# Piano_DIY_Project_Yay.net
KiCad netlist of a schematic drawn in EAGLE
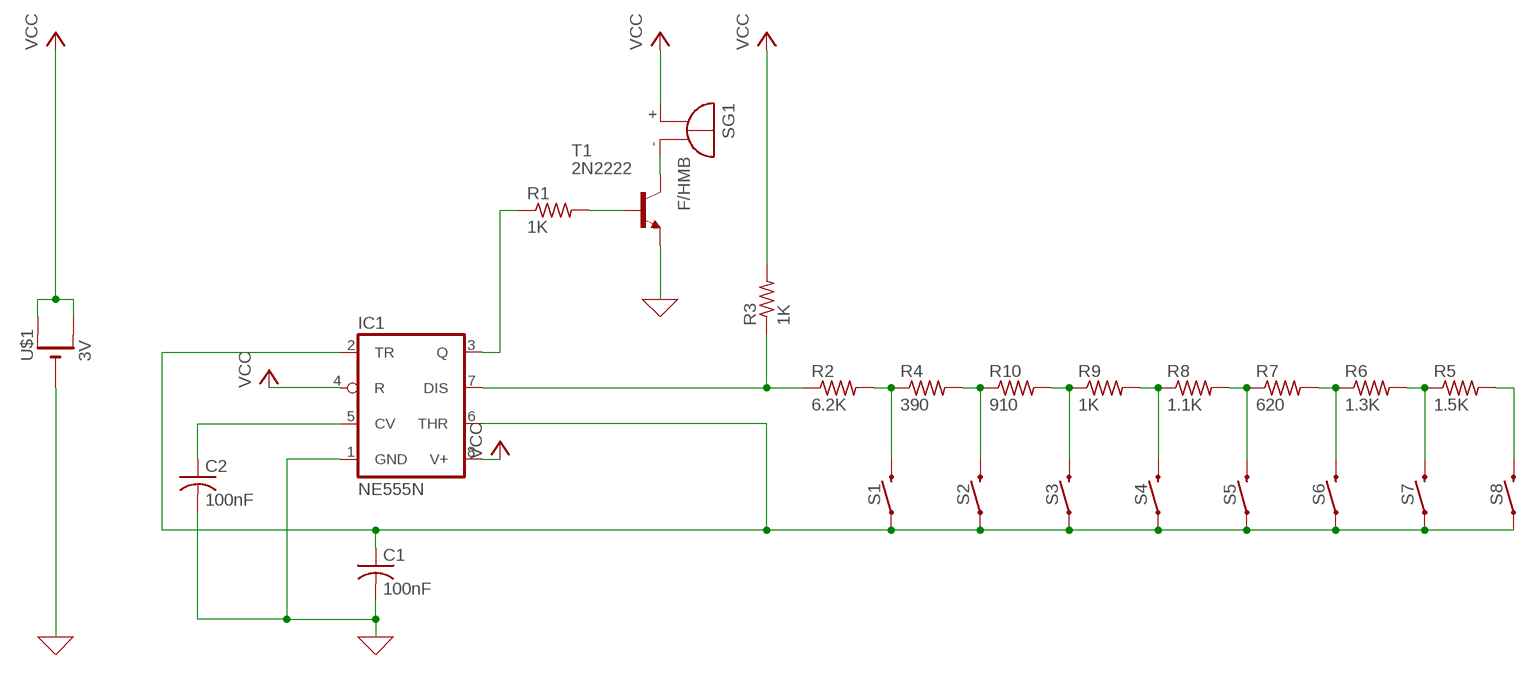
[diagram p0: schematic, sheet 1]

(export (version "E")
  (design (tool "Eeschema 10.0.6"))
  (components
    (comp (ref "C1")
      (value "100nF")
      (footprint "eagle-import:C025-025X050")
      (libsource (lib "eagle-import") (part "C-US025-025X050"))
    )
    (comp (ref "C2")
      (value "100nF")
      (footprint "eagle-import:C025-025X050")
      (libsource (lib "eagle-import") (part "C-US025-025X050"))
    )
    (comp (ref "IC1")
      (value "NE555N")
      (footprint "eagle-import:DIL08")
      (libsource (lib "eagle-import") (part "555NNE"))
    )
    (comp (ref "R1")
      (value "1K")
      (footprint "eagle-import:0207_10")
      (libsource (lib "eagle-import") (part "R-US_0207/10"))
    )
    (comp (ref "R2")
      (value "6.2K")
      (footprint "eagle-import:0207_10")
      (libsource (lib "eagle-import") (part "R-US_0207/10"))
    )
    (comp (ref "R3")
      (value "1K")
      (footprint "eagle-import:0207_10")
      (libsource (lib "eagle-import") (part "R-US_0207/10"))
    )
    (comp (ref "R4")
      (value "390")
      (footprint "eagle-import:0207_10")
      (libsource (lib "eagle-import") (part "R-US_0207/10"))
    )
    (comp (ref "R5")
      (value "1.5K")
      (footprint "eagle-import:0207_10")
      (libsource (lib "eagle-import") (part "R-US_0207/10"))
    )
    (comp (ref "R6")
      (value "1.3K")
      (footprint "eagle-import:0207_10")
      (libsource (lib "eagle-import") (part "R-US_0207/10"))
    )
    (comp (ref "R7")
      (value "620")
      (footprint "eagle-import:0207_10")
      (libsource (lib "eagle-import") (part "R-US_0207/10"))
    )
    (comp (ref "R8")
      (value "1.1K")
      (footprint "eagle-import:0207_10")
      (libsource (lib "eagle-import") (part "R-US_0207/10"))
    )
    (comp (ref "R9")
      (value "1K")
      (footprint "eagle-import:0207_10")
      (libsource (lib "eagle-import") (part "R-US_0207/10"))
    )
    (comp (ref "R10")
      (value "910")
      (footprint "eagle-import:0207_10")
      (libsource (lib "eagle-import") (part "R-US_0207/10"))
    )
    (comp (ref "S1")
      (value "MOMENTARY-SWITCH-SPST-PTH-6.0MM")
      (footprint "eagle-import:TACTILE_SWITCH_PTH_6.0MM")
      (libsource (lib "eagle-import") (part "MOMENTARY-SWITCH-SPST-PTH-6.0MM"))
    )
    (comp (ref "S2")
      (value "MOMENTARY-SWITCH-SPST-PTH-6.0MM")
      (footprint "eagle-import:TACTILE_SWITCH_PTH_6.0MM")
      (libsource (lib "eagle-import") (part "MOMENTARY-SWITCH-SPST-PTH-6.0MM"))
    )
    (comp (ref "S3")
      (value "MOMENTARY-SWITCH-SPST-PTH-6.0MM")
      (footprint "eagle-import:TACTILE_SWITCH_PTH_6.0MM")
      (libsource (lib "eagle-import") (part "MOMENTARY-SWITCH-SPST-PTH-6.0MM"))
    )
    (comp (ref "S4")
      (value "MOMENTARY-SWITCH-SPST-PTH-6.0MM")
      (footprint "eagle-import:TACTILE_SWITCH_PTH_6.0MM")
      (libsource (lib "eagle-import") (part "MOMENTARY-SWITCH-SPST-PTH-6.0MM"))
    )
    (comp (ref "S5")
      (value "MOMENTARY-SWITCH-SPST-PTH-6.0MM")
      (footprint "eagle-import:TACTILE_SWITCH_PTH_6.0MM")
      (libsource (lib "eagle-import") (part "MOMENTARY-SWITCH-SPST-PTH-6.0MM"))
    )
    (comp (ref "S6")
      (value "MOMENTARY-SWITCH-SPST-PTH-6.0MM")
      (footprint "eagle-import:TACTILE_SWITCH_PTH_6.0MM")
      (libsource (lib "eagle-import") (part "MOMENTARY-SWITCH-SPST-PTH-6.0MM"))
    )
    (comp (ref "S7")
      (value "MOMENTARY-SWITCH-SPST-PTH-6.0MM")
      (footprint "eagle-import:TACTILE_SWITCH_PTH_6.0MM")
      (libsource (lib "eagle-import") (part "MOMENTARY-SWITCH-SPST-PTH-6.0MM"))
    )
    (comp (ref "S8")
      (value "MOMENTARY-SWITCH-SPST-PTH-6.0MM")
      (footprint "eagle-import:TACTILE_SWITCH_PTH_6.0MM")
      (libsource (lib "eagle-import") (part "MOMENTARY-SWITCH-SPST-PTH-6.0MM"))
    )
    (comp (ref "SG1")
      (value "F/HMB")
      (footprint "eagle-import:F_HMB")
      (libsource (lib "eagle-import") (part "F/HMB"))
    )
    (comp (ref "T1")
      (value "2N2222")
      (footprint "eagle-import:TO92")
      (libsource (lib "eagle-import") (part "-NPN-TO92"))
    )
    (comp (ref "U$1")
      (value "3V")
      (footprint "eagle-import:CR1220-THM")
      (libsource (lib "eagle-import") (part "CR1220THM"))
    )
  )
  (nets
    (net (code "1") (name "GND") (class "Default")
      (node (ref "C1") (pin "2") (pinfunction "2_2") (pintype "passive"))
      (node (ref "C2") (pin "2") (pinfunction "2_2") (pintype "passive"))
      (node (ref "IC1") (pin "1") (pinfunction "GND_1") (pintype "power_in"))
      (node (ref "T1") (pin "1") (pinfunction "E_1") (pintype "passive"))
      (node (ref "U$1") (pin "-") (pinfunction "-_-") (pintype "passive"))
    )
    (net (code "2") (name "Net-(IC1-CV)") (class "Default")
      (node (ref "C2") (pin "1") (pinfunction "1_1") (pintype "passive"))
      (node (ref "IC1") (pin "5") (pinfunction "CV_5") (pintype "input"))
    )
    (net (code "3") (name "Net-(IC1-DIS)") (class "Default")
      (node (ref "IC1") (pin "7") (pinfunction "DIS_7") (pintype "input"))
      (node (ref "R2") (pin "1") (pinfunction "1_1") (pintype "passive"))
      (node (ref "R3") (pin "1") (pinfunction "1_1") (pintype "passive"))
    )
    (net (code "4") (name "Net-(IC1-Q)") (class "Default")
      (node (ref "IC1") (pin "3") (pinfunction "Q_3") (pintype "output"))
      (node (ref "R1") (pin "1") (pinfunction "1_1") (pintype "passive"))
    )
    (net (code "5") (name "Net-(IC1-THR)") (class "Default")
      (node (ref "C1") (pin "1") (pinfunction "1_1") (pintype "passive"))
      (node (ref "IC1") (pin "2") (pinfunction "TR_2") (pintype "input"))
      (node (ref "IC1") (pin "6") (pinfunction "THR_6") (pintype "input"))
      (node (ref "S1") (pin "1") (pinfunction "1_1") (pintype "passive"))
      (node (ref "S2") (pin "1") (pinfunction "1_1") (pintype "passive"))
      (node (ref "S3") (pin "1") (pinfunction "1_1") (pintype "passive"))
      (node (ref "S4") (pin "1") (pinfunction "1_1") (pintype "passive"))
      (node (ref "S5") (pin "1") (pinfunction "1_1") (pintype "passive"))
      (node (ref "S6") (pin "1") (pinfunction "1_1") (pintype "passive"))
      (node (ref "S7") (pin "1") (pinfunction "1_1") (pintype "passive"))
      (node (ref "S8") (pin "1") (pinfunction "1_1") (pintype "passive"))
    )
    (net (code "6") (name "Net-(S1-2)") (class "Default")
      (node (ref "R2") (pin "2") (pinfunction "2_2") (pintype "passive"))
      (node (ref "R4") (pin "1") (pinfunction "1_1") (pintype "passive"))
      (node (ref "S1") (pin "3") (pinfunction "2_3") (pintype "passive"))
    )
    (net (code "7") (name "Net-(S2-2)") (class "Default")
      (node (ref "R10") (pin "1") (pinfunction "1_1") (pintype "passive"))
      (node (ref "R4") (pin "2") (pinfunction "2_2") (pintype "passive"))
      (node (ref "S2") (pin "3") (pinfunction "2_3") (pintype "passive"))
    )
    (net (code "8") (name "Net-(S3-2)") (class "Default")
      (node (ref "R10") (pin "2") (pinfunction "2_2") (pintype "passive"))
      (node (ref "R9") (pin "1") (pinfunction "1_1") (pintype "passive"))
      (node (ref "S3") (pin "3") (pinfunction "2_3") (pintype "passive"))
    )
    (net (code "9") (name "Net-(S4-2)") (class "Default")
      (node (ref "R8") (pin "1") (pinfunction "1_1") (pintype "passive"))
      (node (ref "R9") (pin "2") (pinfunction "2_2") (pintype "passive"))
      (node (ref "S4") (pin "3") (pinfunction "2_3") (pintype "passive"))
    )
    (net (code "10") (name "Net-(S5-2)") (class "Default")
      (node (ref "R7") (pin "1") (pinfunction "1_1") (pintype "passive"))
      (node (ref "R8") (pin "2") (pinfunction "2_2") (pintype "passive"))
      (node (ref "S5") (pin "3") (pinfunction "2_3") (pintype "passive"))
    )
    (net (code "11") (name "Net-(S6-2)") (class "Default")
      (node (ref "R6") (pin "1") (pinfunction "1_1") (pintype "passive"))
      (node (ref "R7") (pin "2") (pinfunction "2_2") (pintype "passive"))
      (node (ref "S6") (pin "3") (pinfunction "2_3") (pintype "passive"))
    )
    (net (code "12") (name "Net-(S7-2)") (class "Default")
      (node (ref "R5") (pin "1") (pinfunction "1_1") (pintype "passive"))
      (node (ref "R6") (pin "2") (pinfunction "2_2") (pintype "passive"))
      (node (ref "S7") (pin "3") (pinfunction "2_3") (pintype "passive"))
    )
    (net (code "13") (name "Net-(S8-2)") (class "Default")
      (node (ref "R5") (pin "2") (pinfunction "2_2") (pintype "passive"))
      (node (ref "S8") (pin "3") (pinfunction "2_3") (pintype "passive"))
    )
    (net (code "14") (name "Net-(T1-B)") (class "Default")
      (node (ref "R1") (pin "2") (pinfunction "2_2") (pintype "passive"))
      (node (ref "T1") (pin "2") (pinfunction "B_2") (pintype "passive"))
    )
    (net (code "15") (name "Net-(T1-C)") (class "Default")
      (node (ref "SG1") (pin "-") (pinfunction "-_-") (pintype "passive"))
      (node (ref "T1") (pin "3") (pinfunction "C_3") (pintype "passive"))
    )
    (net (code "16") (name "VCC") (class "Default")
      (node (ref "IC1") (pin "4") (pinfunction "R_4") (pintype "input"))
      (node (ref "IC1") (pin "8") (pinfunction "V+_8") (pintype "power_in"))
      (node (ref "R3") (pin "2") (pinfunction "2_2") (pintype "passive"))
      (node (ref "SG1") (pin "+") (pinfunction "+_+") (pintype "passive"))
      (node (ref "U$1") (pin "+1") (pinfunction "+_+1") (pintype "passive"))
      (node (ref "U$1") (pin "+2") (pinfunction "+1_+2") (pintype "passive"))
    )
  )
)
